# iss2_yuvmod.net
KiCad netlist of a schematic drawn in EAGLE
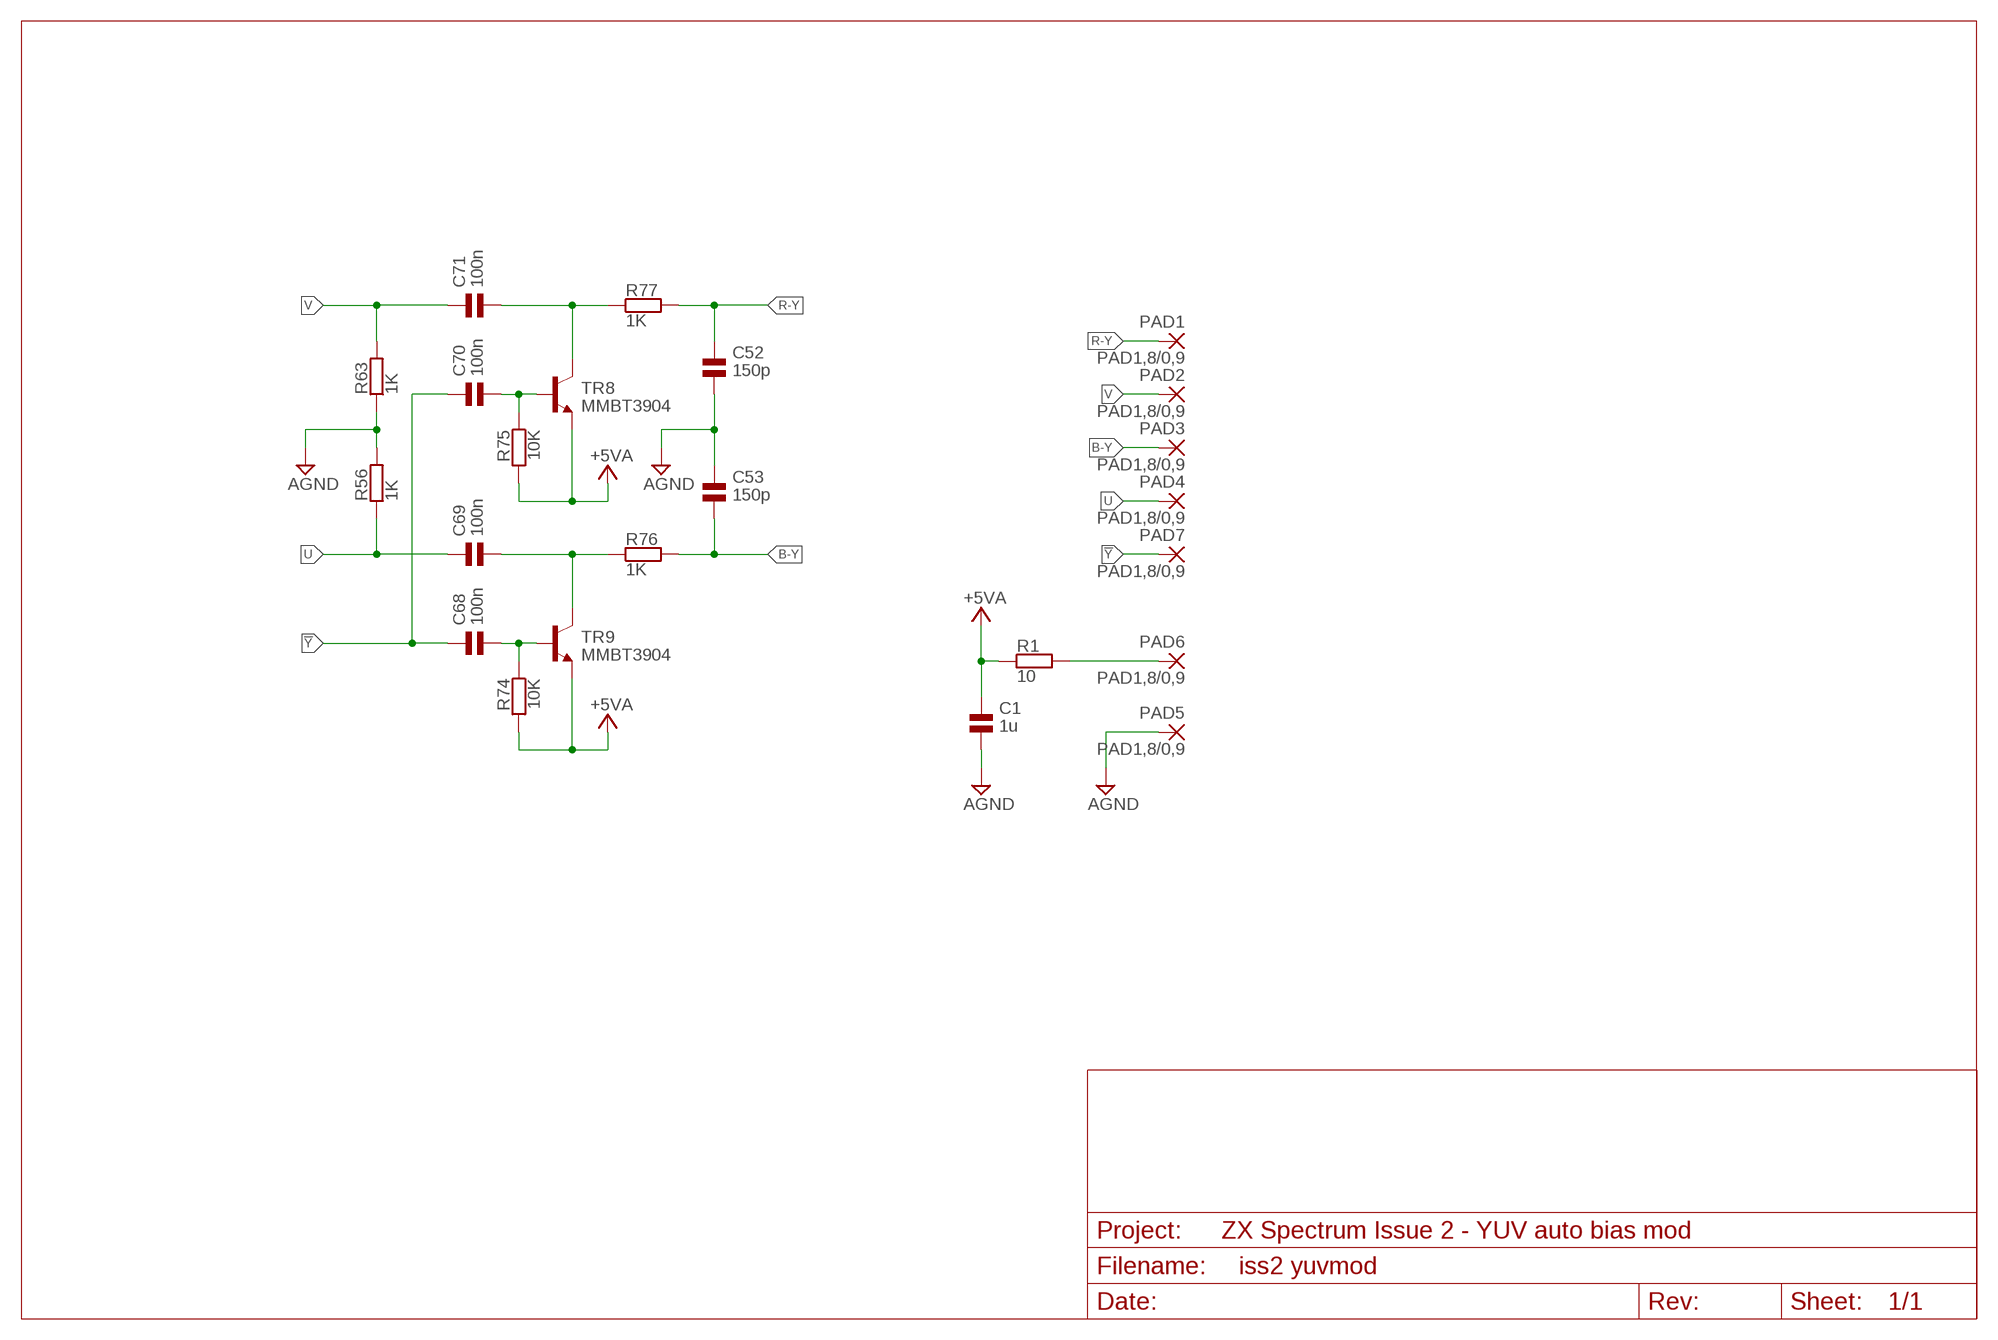
[diagram p0: schematic, sheet 1]

(export (version "E")
  (design (tool "Eeschema 10.0.6"))
  (components
    (comp (ref "C1")
      (value "1u")
      (footprint "eagle-import:0603")
      (fields (field (name "LCSC_PART") "C15849"))
      (libsource (lib "eagle-import") (part "CAP_NPOL0603-"))
    )
    (comp (ref "C52")
      (value "150p")
      (footprint "eagle-import:0603")
      (fields (field (name "LCSC_PART") "C1594"))
      (libsource (lib "eagle-import") (part "CAP_NPOL0603-"))
    )
    (comp (ref "C53")
      (value "150p")
      (footprint "eagle-import:0603")
      (fields (field (name "LCSC_PART") "C1594"))
      (libsource (lib "eagle-import") (part "CAP_NPOL0603-"))
    )
    (comp (ref "C68")
      (value "100n")
      (footprint "eagle-import:0603")
      (fields (field (name "LCSC_PART") "C14663"))
      (libsource (lib "eagle-import") (part "CAP_NPOL0603-"))
    )
    (comp (ref "C69")
      (value "100n")
      (footprint "eagle-import:0603")
      (fields (field (name "LCSC_PART") "C14663"))
      (libsource (lib "eagle-import") (part "CAP_NPOL0603-"))
    )
    (comp (ref "C70")
      (value "100n")
      (footprint "eagle-import:0603")
      (fields (field (name "LCSC_PART") "C14663"))
      (libsource (lib "eagle-import") (part "CAP_NPOL0603-"))
    )
    (comp (ref "C71")
      (value "100n")
      (footprint "eagle-import:0603")
      (fields (field (name "LCSC_PART") "C14663"))
      (libsource (lib "eagle-import") (part "CAP_NPOL0603-"))
    )
    (comp (ref "PAD1")
      (value "PAD1,8/0,9")
      (footprint "eagle-import:1,8_0,9")
      (libsource (lib "eagle-import") (part "PAD1,8/0,9"))
    )
    (comp (ref "PAD2")
      (value "PAD1,8/0,9")
      (footprint "eagle-import:1,8_0,9")
      (libsource (lib "eagle-import") (part "PAD1,8/0,9"))
    )
    (comp (ref "PAD3")
      (value "PAD1,8/0,9")
      (footprint "eagle-import:1,8_0,9")
      (libsource (lib "eagle-import") (part "PAD1,8/0,9"))
    )
    (comp (ref "PAD4")
      (value "PAD1,8/0,9")
      (footprint "eagle-import:1,8_0,9")
      (libsource (lib "eagle-import") (part "PAD1,8/0,9"))
    )
    (comp (ref "PAD5")
      (value "PAD1,8/0,9")
      (footprint "eagle-import:1,8_0,9")
      (libsource (lib "eagle-import") (part "PAD1,8/0,9"))
    )
    (comp (ref "PAD6")
      (value "PAD1,8/0,9")
      (footprint "eagle-import:1,8_0,9")
      (libsource (lib "eagle-import") (part "PAD1,8/0,9"))
    )
    (comp (ref "PAD7")
      (value "PAD1,8/0,9")
      (footprint "eagle-import:1,8_0,9")
      (libsource (lib "eagle-import") (part "PAD1,8/0,9"))
    )
    (comp (ref "R1")
      (value "10")
      (footprint "eagle-import:0603")
      (fields (field (name "LCSC_PART") "C22859"))
      (libsource (lib "eagle-import") (part "RESSMD_0603-"))
    )
    (comp (ref "R56")
      (value "1K")
      (footprint "eagle-import:0603")
      (fields (field (name "LCSC_PART") "C21190"))
      (libsource (lib "eagle-import") (part "RESSMD_0603-"))
    )
    (comp (ref "R63")
      (value "1K")
      (footprint "eagle-import:0603")
      (fields (field (name "LCSC_PART") "C21190"))
      (libsource (lib "eagle-import") (part "RESSMD_0603-"))
    )
    (comp (ref "R74")
      (value "10K")
      (footprint "eagle-import:0603")
      (fields (field (name "LCSC_PART") "C25804"))
      (libsource (lib "eagle-import") (part "RESSMD_0603-"))
    )
    (comp (ref "R75")
      (value "10K")
      (footprint "eagle-import:0603")
      (fields (field (name "LCSC_PART") "C25804"))
      (libsource (lib "eagle-import") (part "RESSMD_0603-"))
    )
    (comp (ref "R76")
      (value "1K")
      (footprint "eagle-import:0603")
      (fields (field (name "LCSC_PART") "C21190"))
      (libsource (lib "eagle-import") (part "RESSMD_0603-"))
    )
    (comp (ref "R77")
      (value "1K")
      (footprint "eagle-import:0603")
      (fields (field (name "LCSC_PART") "C21190"))
      (libsource (lib "eagle-import") (part "RESSMD_0603-"))
    )
    (comp (ref "TR8")
      (value "MMBT3904")
      (footprint "eagle-import:SOT23")
      (fields (field (name "LCSC_PART") "C20526"))
      (libsource (lib "eagle-import") (part "-NPN_?SOT23"))
    )
    (comp (ref "TR9")
      (value "MMBT3904")
      (footprint "eagle-import:SOT23")
      (fields (field (name "LCSC_PART") "C20526"))
      (libsource (lib "eagle-import") (part "-NPN_?SOT23"))
    )
  )
  (nets
    (net (code "1") (name "+5VA") (class "Default")
      (node (ref "C1") (pin "1") (pinfunction "1_1") (pintype "passive"))
      (node (ref "R1") (pin "1") (pinfunction "1_1") (pintype "passive"))
      (node (ref "R74") (pin "2") (pinfunction "2_2") (pintype "passive"))
      (node (ref "R75") (pin "2") (pinfunction "2_2") (pintype "passive"))
      (node (ref "TR8") (pin "2") (pinfunction "E_2") (pintype "passive"))
      (node (ref "TR9") (pin "2") (pinfunction "E_2") (pintype "passive"))
    )
    (net (code "2") (name "/~{Y}") (class "Default")
      (node (ref "C68") (pin "1") (pinfunction "1_1") (pintype "passive"))
      (node (ref "C70") (pin "1") (pinfunction "1_1") (pintype "passive"))
      (node (ref "PAD7") (pin "1") (pinfunction "P_1") (pintype "passive"))
    )
    (net (code "3") (name "AGND") (class "Default")
      (node (ref "C1") (pin "2") (pinfunction "2_2") (pintype "passive"))
      (node (ref "C52") (pin "2") (pinfunction "2_2") (pintype "passive"))
      (node (ref "C53") (pin "1") (pinfunction "1_1") (pintype "passive"))
      (node (ref "PAD5") (pin "1") (pinfunction "P_1") (pintype "passive"))
      (node (ref "R56") (pin "2") (pinfunction "2_2") (pintype "passive"))
      (node (ref "R63") (pin "1") (pinfunction "1_1") (pintype "passive"))
    )
    (net (code "4") (name "B-Y") (class "Default")
      (node (ref "C53") (pin "2") (pinfunction "2_2") (pintype "passive"))
      (node (ref "PAD3") (pin "1") (pinfunction "P_1") (pintype "passive"))
      (node (ref "R76") (pin "2") (pinfunction "2_2") (pintype "passive"))
    )
    (net (code "5") (name "Net-(PAD6-P)") (class "Default")
      (node (ref "PAD6") (pin "1") (pinfunction "P_1") (pintype "passive"))
      (node (ref "R1") (pin "2") (pinfunction "2_2") (pintype "passive"))
    )
    (net (code "6") (name "Net-(TR8-B)") (class "Default")
      (node (ref "C70") (pin "2") (pinfunction "2_2") (pintype "passive"))
      (node (ref "R75") (pin "1") (pinfunction "1_1") (pintype "passive"))
      (node (ref "TR8") (pin "1") (pinfunction "B_1") (pintype "passive"))
    )
    (net (code "7") (name "Net-(TR8-C)") (class "Default")
      (node (ref "C71") (pin "2") (pinfunction "2_2") (pintype "passive"))
      (node (ref "R77") (pin "1") (pinfunction "1_1") (pintype "passive"))
      (node (ref "TR8") (pin "3") (pinfunction "C_3") (pintype "passive"))
    )
    (net (code "8") (name "Net-(TR9-B)") (class "Default")
      (node (ref "C68") (pin "2") (pinfunction "2_2") (pintype "passive"))
      (node (ref "R74") (pin "1") (pinfunction "1_1") (pintype "passive"))
      (node (ref "TR9") (pin "1") (pinfunction "B_1") (pintype "passive"))
    )
    (net (code "9") (name "Net-(TR9-C)") (class "Default")
      (node (ref "C69") (pin "2") (pinfunction "2_2") (pintype "passive"))
      (node (ref "R76") (pin "1") (pinfunction "1_1") (pintype "passive"))
      (node (ref "TR9") (pin "3") (pinfunction "C_3") (pintype "passive"))
    )
    (net (code "10") (name "R-Y") (class "Default")
      (node (ref "C52") (pin "1") (pinfunction "1_1") (pintype "passive"))
      (node (ref "PAD1") (pin "1") (pinfunction "P_1") (pintype "passive"))
      (node (ref "R77") (pin "2") (pinfunction "2_2") (pintype "passive"))
    )
    (net (code "11") (name "U") (class "Default")
      (node (ref "C69") (pin "1") (pinfunction "1_1") (pintype "passive"))
      (node (ref "PAD4") (pin "1") (pinfunction "P_1") (pintype "passive"))
      (node (ref "R56") (pin "1") (pinfunction "1_1") (pintype "passive"))
    )
    (net (code "12") (name "V") (class "Default")
      (node (ref "C71") (pin "1") (pinfunction "1_1") (pintype "passive"))
      (node (ref "PAD2") (pin "1") (pinfunction "P_1") (pintype "passive"))
      (node (ref "R63") (pin "2") (pinfunction "2_2") (pintype "passive"))
    )
  )
)
